# 5_Power_Supplies.net
KiCad netlist of a schematic drawn in Altium Designer
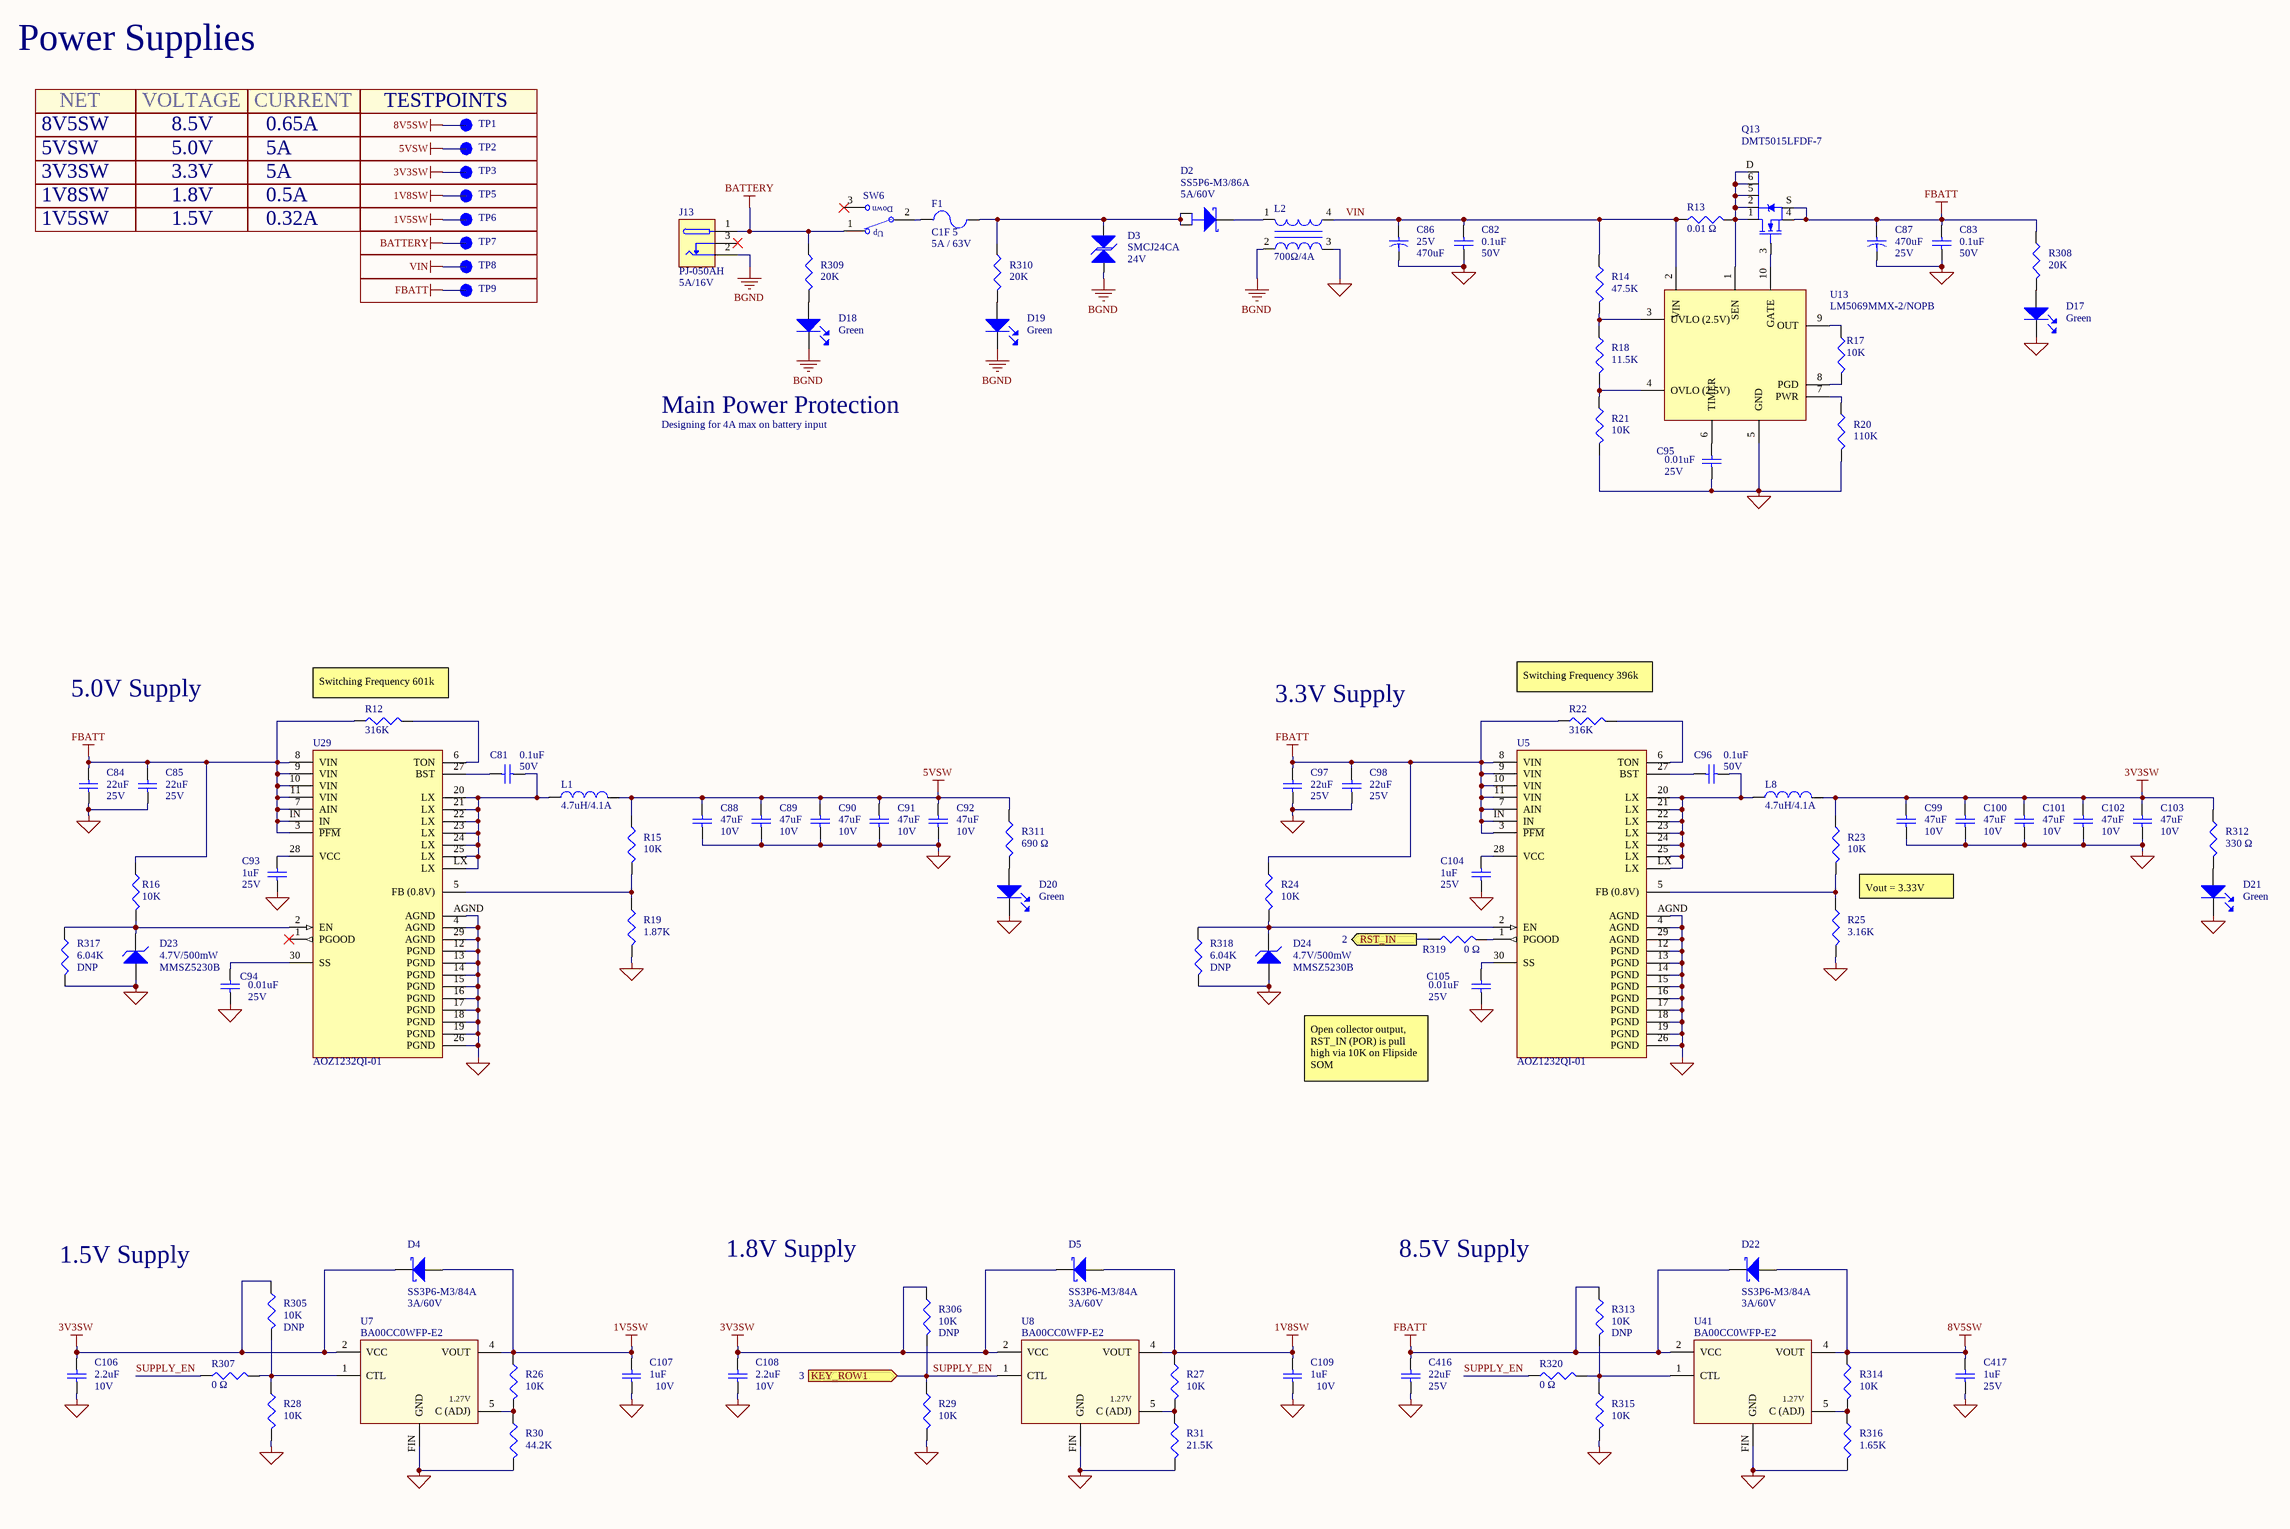
[diagram p0: 5 Power Supplies.SchDoc]

(export (version "E")
  (design (tool "Eeschema 10.0.6"))
  (components
    (comp (ref "C81")
      (value "0.1uF")
      (footprint "CAP_0402")
      (description "Cap, Cer, 0.1uF, 50V, 10%, X5R, 0402")
      (fields
        (field (name "TOLERANCE") "±10%")
        (field (name "MANUFACTURER") "TDK Corporation")
        (field (name "VOLTAGE") "50V")
      )
      (libsource (lib "Firstview") (part "Cap 0.1uF 50V 0402"))
    )
    (comp (ref "C82")
      (value "0.1uF")
      (footprint "CAP_0402")
      (description "Cap, Cer, 0.1uF, 50V, 10%, X5R, 0402")
      (fields
        (field (name "TOLERANCE") "±10%")
        (field (name "MANUFACTURER") "TDK Corporation")
        (field (name "VOLTAGE") "50V")
      )
      (libsource (lib "Firstview") (part "Cap 0.1uF 50V 0402"))
    )
    (comp (ref "C83")
      (value "0.1uF")
      (footprint "CAP_0402")
      (description "Cap, Cer, 0.1uF, 50V, 10%, X5R, 0402")
      (fields
        (field (name "TOLERANCE") "±10%")
        (field (name "MANUFACTURER") "TDK Corporation")
        (field (name "VOLTAGE") "50V")
      )
      (libsource (lib "Firstview") (part "Cap 0.1uF 50V 0402"))
    )
    (comp (ref "C84")
      (value "22uF")
      (footprint "CAP_0805")
      (description "Cap, Cer, 22uF, 25V, 20%, X5R, 0805")
      (fields
        (field (name "TOLERANCE") "±20%")
        (field (name "MANUFACTURER") "Samsung Electro-Mechanics America, Inc")
        (field (name "VOLTAGE") "25V")
      )
      (libsource (lib "Firstview") (part "Cap 22uF 25V 0805"))
    )
    (comp (ref "C85")
      (value "22uF")
      (footprint "CAP_0805")
      (description "Cap, Cer, 22uF, 25V, 20%, X5R, 0805")
      (fields
        (field (name "TOLERANCE") "±20%")
        (field (name "MANUFACTURER") "Samsung Electro-Mechanics America, Inc")
        (field (name "VOLTAGE") "25V")
      )
      (libsource (lib "Firstview") (part "Cap 22uF 25V 0805"))
    )
    (comp (ref "C86")
      (value "470uF")
      (footprint "SMD(8.3x8.3)_EEE-FT1E471AP")
      (description "Cap, Alum, 470uF, 25V, 20%, 80 mOhm, SMD")
      (fields
        (field (name "TOLERANCE") "20%")
        (field (name "MANUFACTURER") "Panasonic Electronic Components")
        (field (name "VOLTAGE") "25V")
      )
      (libsource (lib "Firstview") (part "Cap 470uF 25V"))
    )
    (comp (ref "C87")
      (value "470uF")
      (footprint "SMD(8.3x8.3)_EEE-FT1E471AP")
      (description "Cap, Alum, 470uF, 25V, 20%, 80 mOhm, SMD")
      (fields
        (field (name "TOLERANCE") "20%")
        (field (name "MANUFACTURER") "Panasonic Electronic Components")
        (field (name "VOLTAGE") "25V")
      )
      (libsource (lib "Firstview") (part "Cap 470uF 25V"))
    )
    (comp (ref "C88")
      (value "47uF")
      (footprint "CAP_1206")
      (description "Cap, Cer, 47uF, 10V, 20%, X5R, 1206")
      (fields
        (field (name "TOLERANCE") "±10%")
        (field (name "MANUFACTURER") "Murata Electronics North America")
        (field (name "VOLTAGE") "10V")
      )
      (libsource (lib "Firstview") (part "Cap 47uF 10V 1206"))
    )
    (comp (ref "C89")
      (value "47uF")
      (footprint "CAP_1206")
      (description "Cap, Cer, 47uF, 10V, 20%, X5R, 1206")
      (fields
        (field (name "TOLERANCE") "±10%")
        (field (name "MANUFACTURER") "Murata Electronics North America")
        (field (name "VOLTAGE") "10V")
      )
      (libsource (lib "Firstview") (part "Cap 47uF 10V 1206"))
    )
    (comp (ref "C90")
      (value "47uF")
      (footprint "CAP_1206")
      (description "Cap, Cer, 47uF, 10V, 20%, X5R, 1206")
      (fields
        (field (name "TOLERANCE") "±10%")
        (field (name "MANUFACTURER") "Murata Electronics North America")
        (field (name "VOLTAGE") "10V")
      )
      (libsource (lib "Firstview") (part "Cap 47uF 10V 1206"))
    )
    (comp (ref "C91")
      (value "47uF")
      (footprint "CAP_1206")
      (description "Cap, Cer, 47uF, 10V, 20%, X5R, 1206")
      (fields
        (field (name "TOLERANCE") "±10%")
        (field (name "MANUFACTURER") "Murata Electronics North America")
        (field (name "VOLTAGE") "10V")
      )
      (libsource (lib "Firstview") (part "Cap 47uF 10V 1206"))
    )
    (comp (ref "C92")
      (value "47uF")
      (footprint "CAP_1206")
      (description "Cap, Cer, 47uF, 10V, 20%, X5R, 1206")
      (fields
        (field (name "TOLERANCE") "±10%")
        (field (name "MANUFACTURER") "Murata Electronics North America")
        (field (name "VOLTAGE") "10V")
      )
      (libsource (lib "Firstview") (part "Cap 47uF 10V 1206"))
    )
    (comp (ref "C93")
      (value "1uF")
      (footprint "CAP_0402")
      (description "Cap, Cer, 1uF, 25V, 10%, X5R, 0402")
      (fields
        (field (name "MANUFACTURER") "Taiyo Yuden")
        (field (name "VOLTAGE") "25V")
        (field (name "Comment") "Cap 1uF 25V 0402")
      )
      (libsource (lib "Firstview") (part "Cap 1uF 25V 0402"))
    )
    (comp (ref "C94")
      (value "0.01uF")
      (footprint "CAP_0402")
      (description "Cap, Cer, 0.01uF, 25V, ±10%, X7R, 0402")
      (fields
        (field (name "TOLERANCE") "±10%")
        (field (name "MANUFACTURER") "Murata")
        (field (name "VOLTAGE") "25V")
      )
      (libsource (lib "Firstview") (part "Cap 0.01uF 50V 0402"))
    )
    (comp (ref "C95")
      (value "0.01uF")
      (footprint "CAP_0402")
      (description "Cap, Cer, 0.01uF, 25V, ±10%, X7R, 0402")
      (fields
        (field (name "TOLERANCE") "±10%")
        (field (name "MANUFACTURER") "Murata")
        (field (name "VOLTAGE") "25V")
      )
      (libsource (lib "Firstview") (part "Cap 0.01uF 50V 0402"))
    )
    (comp (ref "C96")
      (value "0.1uF")
      (footprint "CAP_0402")
      (description "Cap, Cer, 0.1uF, 50V, 10%, X5R, 0402")
      (fields
        (field (name "TOLERANCE") "±10%")
        (field (name "MANUFACTURER") "TDK Corporation")
        (field (name "VOLTAGE") "50V")
      )
      (libsource (lib "Firstview") (part "Cap 0.1uF 50V 0402"))
    )
    (comp (ref "C97")
      (value "22uF")
      (footprint "CAP_0805")
      (description "Cap, Cer, 22uF, 25V, 20%, X5R, 0805")
      (fields
        (field (name "TOLERANCE") "±20%")
        (field (name "MANUFACTURER") "Samsung Electro-Mechanics America, Inc")
        (field (name "VOLTAGE") "25V")
      )
      (libsource (lib "Firstview") (part "Cap 22uF 25V 0805"))
    )
    (comp (ref "C98")
      (value "22uF")
      (footprint "CAP_0805")
      (description "Cap, Cer, 22uF, 25V, 20%, X5R, 0805")
      (fields
        (field (name "TOLERANCE") "±20%")
        (field (name "MANUFACTURER") "Samsung Electro-Mechanics America, Inc")
        (field (name "VOLTAGE") "25V")
      )
      (libsource (lib "Firstview") (part "Cap 22uF 25V 0805"))
    )
    (comp (ref "C99")
      (value "47uF")
      (footprint "CAP_1206")
      (description "Cap, Cer, 47uF, 10V, 20%, X5R, 1206")
      (fields
        (field (name "TOLERANCE") "±10%")
        (field (name "MANUFACTURER") "Murata Electronics North America")
        (field (name "VOLTAGE") "10V")
      )
      (libsource (lib "Firstview") (part "Cap 47uF 10V 1206"))
    )
    (comp (ref "C100")
      (value "47uF")
      (footprint "CAP_1206")
      (description "Cap, Cer, 47uF, 10V, 20%, X5R, 1206")
      (fields
        (field (name "TOLERANCE") "±10%")
        (field (name "MANUFACTURER") "Murata Electronics North America")
        (field (name "VOLTAGE") "10V")
      )
      (libsource (lib "Firstview") (part "Cap 47uF 10V 1206"))
    )
    (comp (ref "C101")
      (value "47uF")
      (footprint "CAP_1206")
      (description "Cap, Cer, 47uF, 10V, 20%, X5R, 1206")
      (fields
        (field (name "TOLERANCE") "±10%")
        (field (name "MANUFACTURER") "Murata Electronics North America")
        (field (name "VOLTAGE") "10V")
      )
      (libsource (lib "Firstview") (part "Cap 47uF 10V 1206"))
    )
    (comp (ref "C102")
      (value "47uF")
      (footprint "CAP_1206")
      (description "Cap, Cer, 47uF, 10V, 20%, X5R, 1206")
      (fields
        (field (name "TOLERANCE") "±10%")
        (field (name "MANUFACTURER") "Murata Electronics North America")
        (field (name "VOLTAGE") "10V")
      )
      (libsource (lib "Firstview") (part "Cap 47uF 10V 1206"))
    )
    (comp (ref "C103")
      (value "47uF")
      (footprint "CAP_1206")
      (description "Cap, Cer, 47uF, 10V, 20%, X5R, 1206")
      (fields
        (field (name "TOLERANCE") "±10%")
        (field (name "MANUFACTURER") "Murata Electronics North America")
        (field (name "VOLTAGE") "10V")
      )
      (libsource (lib "Firstview") (part "Cap 47uF 10V 1206"))
    )
    (comp (ref "C104")
      (value "1uF")
      (footprint "CAP_0402")
      (description "Cap, Cer, 1uF, 25V, 10%, X5R, 0402")
      (fields
        (field (name "MANUFACTURER") "Taiyo Yuden")
        (field (name "VOLTAGE") "25V")
        (field (name "Comment") "Cap 1uF 25V 0402")
      )
      (libsource (lib "Firstview") (part "Cap 1uF 25V 0402"))
    )
    (comp (ref "C105")
      (value "0.01uF")
      (footprint "CAP_0402")
      (description "Cap, Cer, 0.01uF, 25V, ±10%, X7R, 0402")
      (fields
        (field (name "TOLERANCE") "±10%")
        (field (name "MANUFACTURER") "Murata")
        (field (name "VOLTAGE") "25V")
      )
      (libsource (lib "Firstview") (part "Cap 0.01uF 50V 0402"))
    )
    (comp (ref "C106")
      (value "2.2uF")
      (footprint "CAP_0402")
      (description "Cap, Cer, 2.2uF, 10V, 10%, X5R, 0402")
      (fields
        (field (name "MANUFACTURER") "Kemet")
        (field (name "VOLTAGE") "10V")
        (field (name "Comment") "Cap 2.2uF 10V 0402")
      )
      (libsource (lib "Firstview") (part "Cap 2.2uF 10V 0402"))
    )
    (comp (ref "C107")
      (value "1uF")
      (footprint "CAP_0402")
      (description "Cap, Cer, 1uF, 10V, ±10%, X5R, 0402")
      (fields
        (field (name "MANUFACTURER") "Yageo")
        (field (name "VOLTAGE") "10V")
        (field (name "Comment") "Cap 1uF 10V 0402")
      )
      (libsource (lib "Firstview") (part "Cap 1uF 10V 0402"))
    )
    (comp (ref "C108")
      (value "2.2uF")
      (footprint "CAP_0402")
      (description "Cap, Cer, 2.2uF, 10V, 10%, X5R, 0402")
      (fields
        (field (name "MANUFACTURER") "Kemet")
        (field (name "VOLTAGE") "10V")
        (field (name "Comment") "Cap 2.2uF 10V 0402")
      )
      (libsource (lib "Firstview") (part "Cap 2.2uF 10V 0402"))
    )
    (comp (ref "C109")
      (value "1uF")
      (footprint "CAP_0402")
      (description "Cap, Cer, 1uF, 10V, ±10%, X5R, 0402")
      (fields
        (field (name "MANUFACTURER") "Yageo")
        (field (name "VOLTAGE") "10V")
        (field (name "Comment") "Cap 1uF 10V 0402")
      )
      (libsource (lib "Firstview") (part "Cap 1uF 10V 0402"))
    )
    (comp (ref "C416")
      (value "22uF")
      (footprint "CAP_0805")
      (description "Cap, Cer, 22uF, 25V, 20%, X5R, 0805")
      (fields
        (field (name "TOLERANCE") "±20%")
        (field (name "MANUFACTURER") "Samsung Electro-Mechanics America, Inc")
        (field (name "VOLTAGE") "25V")
      )
      (libsource (lib "Firstview") (part "Cap 22uF 25V 0805"))
    )
    (comp (ref "C417")
      (value "1uF")
      (footprint "CAP_0402")
      (description "Cap, Cer, 1uF, 25V, 10%, X5R, 0402")
      (fields
        (field (name "MANUFACTURER") "Taiyo Yuden")
        (field (name "VOLTAGE") "25V")
        (field (name "Comment") "Cap 1uF 25V 0402")
      )
      (libsource (lib "Firstview") (part "Cap 1uF 25V 0402"))
    )
    (comp (ref "D2")
      (value "SS5P6-M3/86A")
      (footprint "TO-277A_SS5P6")
      (description "Diode, Schottky, 5A, 60V, TO-277A")
      (fields
        (field (name "MANUFACTURER") "Vishay Semiconductor Diodes Division")
        (field (name "ALTIUM_VALUE") "5A/60V")
      )
      (libsource (lib "Firstview") (part "SS5P6-M3/86A"))
    )
    (comp (ref "D3")
      (value "SMCJ24CA")
      (footprint "SMC_SMCJ24CA")
      (description "Diode, TVS, 24V, 1500W, SMC")
      (fields (field (name "MANUFACTURER") "Littelfuse Inc") (field (name "ALTIUM_VALUE") "24V"))
      (libsource (lib "Firstview") (part "SMCJ24CA"))
    )
    (comp (ref "D4")
      (value "SS3P6-M3/84A")
      (footprint "DO-220AA_SS3P6-M3/84A")
      (description "Diode, Schottky, 3A, 60V, DO-220AA")
      (fields (field (name "MANUFACTURER") "Vishay") (field (name "ALTIUM_VALUE") "3A/60V"))
      (libsource (lib "Firstview") (part "SS3P6-M3/84A"))
    )
    (comp (ref "D5")
      (value "SS3P6-M3/84A")
      (footprint "DO-220AA_SS3P6-M3/84A")
      (description "Diode, Schottky, 3A, 60V, DO-220AA")
      (fields (field (name "MANUFACTURER") "Vishay") (field (name "ALTIUM_VALUE") "3A/60V"))
      (libsource (lib "Firstview") (part "SS3P6-M3/84A"))
    )
    (comp (ref "D17")
      (value "Green")
      (footprint "LED_0603")
      (description "Led, Green, 2mA, 1.7V, 0603")
      (fields
        (field (name "MANUFACTURER") "OSRAM Opto Semiconductors Inc")
        (field (name "Comment") "LG L29K-G2J1-24-Z")
      )
      (libsource (lib "Firstview") (part "LG L29K-G2J1-24-Z"))
    )
    (comp (ref "D18")
      (value "Green")
      (footprint "LED_0603")
      (description "Led, Green, 2mA, 1.7V, 0603")
      (fields
        (field (name "MANUFACTURER") "OSRAM Opto Semiconductors Inc")
        (field (name "Comment") "LG L29K-G2J1-24-Z")
      )
      (libsource (lib "Firstview") (part "LG L29K-G2J1-24-Z"))
    )
    (comp (ref "D19")
      (value "Green")
      (footprint "LED_0603")
      (description "Led, Green, 2mA, 1.7V, 0603")
      (fields
        (field (name "MANUFACTURER") "OSRAM Opto Semiconductors Inc")
        (field (name "Comment") "LG L29K-G2J1-24-Z")
      )
      (libsource (lib "Firstview") (part "LG L29K-G2J1-24-Z"))
    )
    (comp (ref "D20")
      (value "Green")
      (footprint "LED_0603")
      (description "Led, Green, 2mA, 1.7V, 0603")
      (fields
        (field (name "MANUFACTURER") "OSRAM Opto Semiconductors Inc")
        (field (name "Comment") "LG L29K-G2J1-24-Z")
      )
      (libsource (lib "Firstview") (part "LG L29K-G2J1-24-Z"))
    )
    (comp (ref "D21")
      (value "Green")
      (footprint "LED_0603")
      (description "Led, Green, 2mA, 1.7V, 0603")
      (fields
        (field (name "MANUFACTURER") "OSRAM Opto Semiconductors Inc")
        (field (name "Comment") "LG L29K-G2J1-24-Z")
      )
      (libsource (lib "Firstview") (part "LG L29K-G2J1-24-Z"))
    )
    (comp (ref "D22")
      (value "SS3P6-M3/84A")
      (footprint "DO-220AA_SS3P6-M3/84A")
      (description "Diode, Schottky, 3A, 60V, DO-220AA")
      (fields (field (name "MANUFACTURER") "Vishay") (field (name "ALTIUM_VALUE") "3A/60V"))
      (libsource (lib "Firstview") (part "SS3P6-M3/84A"))
    )
    (comp (ref "D23")
      (value "MMSZ5230B")
      (footprint "SOD-123_MMSZ5230B")
      (description "Diode, Zener, 4.7V, 500mW, SOD-123")
      (fields (field (name "MANUFACTURER") "Diodes Incorporated") (field (name "ALTIUM_VALUE") "4.7V/500mW"))
      (libsource (lib "Firstview") (part "MMSZ5230B"))
    )
    (comp (ref "D24")
      (value "MMSZ5230B")
      (footprint "SOD-123_MMSZ5230B")
      (description "Diode, Zener, 4.7V, 500mW, SOD-123")
      (fields (field (name "MANUFACTURER") "Diodes Incorporated") (field (name "ALTIUM_VALUE") "4.7V/500mW"))
      (libsource (lib "Firstview") (part "MMSZ5230B"))
    )
    (comp (ref "F1")
      (value "C1F 5")
      (footprint "FUSE_1206")
      (description "Fuse, 5A, 63V, 1206")
      (fields (field (name "MANUFACTURER") "Bel Fuse Inc") (field (name "ALTIUM_VALUE") "5A / 63V"))
      (libsource (lib "Firstview") (part "C1F 5"))
    )
    (comp (ref "J13")
      (value "PJ-050AH")
      (footprint "CONN_PJ-050AH")
      (description "Conn, Power Jack, 2.1x5mm, R/A, TH")
      (fields
        (field (name "VOLTAGE") "16V")
        (field (name "MANUFACTURER") "CUI Inc")
        (field (name "ALTIUM_VALUE") "5A/16V")
      )
      (libsource (lib "Firstview") (part "PJ-050AH"))
    )
    (comp (ref "L1")
      (value "4.7uH/4.1A")
      (footprint "IND_NRS8040T4R7NJGJ")
      (description "Ind, Power, 4.7uH, 4.1A, 23.4mOhm, Shielded, SMD")
      (fields (field (name "MANUFACTURER") "Taiyo Yuden") (field (name "Comment") "NRS8040T4R7NJGJ"))
      (libsource (lib "Firstview") (part "NRS8040T4R7NJGJ"))
    )
    (comp (ref "L2")
      (value "700Ω/4A")
      (footprint "IND_ACM70V-701-2PL-TL00")
      (description "Ind, Choke, Common Mode, 700R, 4A, SMD")
      (fields (field (name "MANUFACTURER") "TDK Corporation") (field (name "Comment") "ACM70V-701-2PL-TL00"))
      (libsource (lib "Firstview") (part "ACM70V-701-2PL-TL00"))
    )
    (comp (ref "L8")
      (value "4.7uH/4.1A")
      (footprint "IND_NRS8040T4R7NJGJ")
      (description "Ind, Power, 4.7uH, 4.1A, 23.4mOhm, Shielded, SMD")
      (fields (field (name "MANUFACTURER") "Taiyo Yuden") (field (name "Comment") "NRS8040T4R7NJGJ"))
      (libsource (lib "Firstview") (part "NRS8040T4R7NJGJ"))
    )
    (comp (ref "Q13")
      (value "DMT5015LFDF-7")
      (footprint "UDFN-6_DMT5015LFDF-7")
      (description "Transistor, N-MOS, 9.1A, 50V, 15 mOhm, UDFN-6")
      (fields (field (name "MANUFACTURER") "Diodes Incorporated") (field (name "VOLTAGE") "50V"))
      (libsource (lib "Firstview") (part "DMT5015LFDF-7"))
    )
    (comp (ref "R12")
      (value "316K")
      (footprint "RES_0402")
      (description "Res, 316K, 0.063W, 1%, 0402")
      (fields
        (field (name "MANUFACTURER") "Stackpole Electronics Inc")
        (field (name "Comment") "Res 316K 0.063W")
      )
      (libsource (lib "Firstview") (part "Res 316K 0.063W"))
    )
    (comp (ref "R13")
      (value "0.01 Ω")
      (footprint "RES_1210")
      (description "Res, 0.01 ohm, 0.5W, 1%, 1210")
      (fields (field (name "MANUFACTURER") "Yageo") (field (name "Comment") "Res 0.01 ohm 0.5W"))
      (libsource (lib "Firstview") (part "Res 0.01 ohm 0.5W"))
    )
    (comp (ref "R14")
      (value "47.5K")
      (footprint "RES_0402")
      (description "Res, 47.5K, 0.063W, 1%, 0402")
      (fields
        (field (name "MANUFACTURER") "Stackpole Electronics Inc")
        (field (name "Comment") "Res 47.5K 0.063W")
      )
      (libsource (lib "Firstview") (part "Res 47.5K 0.063W"))
    )
    (comp (ref "R15")
      (value "10K")
      (footprint "RES_0402")
      (description "Res, 10K, 1/16W, 1%, 0402")
      (fields (field (name "MANUFACTURER") "Yageo") (field (name "Comment") "Res 10K 0.063W"))
      (libsource (lib "Firstview") (part "Res 10K 0.063W"))
    )
    (comp (ref "R16")
      (value "10K")
      (footprint "RES_0402")
      (description "Res, 10K, 1/16W, 1%, 0402")
      (fields (field (name "MANUFACTURER") "Yageo") (field (name "Comment") "Res 10K 0.063W"))
      (libsource (lib "Firstview") (part "Res 10K 0.063W"))
    )
    (comp (ref "R17")
      (value "10K")
      (footprint "RES_0402")
      (description "Res, 10K, 1/16W, 1%, 0402")
      (fields (field (name "MANUFACTURER") "Yageo") (field (name "Comment") "Res 10K 0.063W"))
      (libsource (lib "Firstview") (part "Res 10K 0.063W"))
    )
    (comp (ref "R18")
      (value "11.5K")
      (footprint "RES_0402")
      (description "Res, 11.5K, 0.063W, 1%, 0402")
      (fields
        (field (name "MANUFACTURER") "Stackpole Electronics Inc")
        (field (name "Comment") "Res 11.5K 0.063W")
      )
      (libsource (lib "Firstview") (part "Res 11.5K 0.063W"))
    )
    (comp (ref "R19")
      (value "1.87K")
      (footprint "RES_0402")
      (description "Res, 1.87K, 0.063W, 1%, 0402")
      (fields (field (name "TOLERANCE") "1%") (field (name "MANUFACTURER") "Stackpole Electronics Inc"))
      (libsource (lib "Firstview") (part "Res 1.87K 0.063W"))
    )
    (comp (ref "R20")
      (value "110K")
      (footprint "RES_0402")
      (description "Res, 110K, 0.063W, 5%, 0402")
      (fields (field (name "TOLERANCE") "5%") (field (name "MANUFACTURER") "Rohm Semiconductor"))
      (libsource (lib "Firstview") (part "Res 110K 0.063W"))
    )
    (comp (ref "R21")
      (value "10K")
      (footprint "RES_0402")
      (description "Res, 10K, 1/16W, 1%, 0402")
      (fields (field (name "MANUFACTURER") "Yageo") (field (name "Comment") "Res 10K 0.063W"))
      (libsource (lib "Firstview") (part "Res 10K 0.063W"))
    )
    (comp (ref "R22")
      (value "316K")
      (footprint "RES_0402")
      (description "Res, 316K, 0.063W, 1%, 0402")
      (fields
        (field (name "MANUFACTURER") "Stackpole Electronics Inc")
        (field (name "Comment") "Res 316K 0.063W")
      )
      (libsource (lib "Firstview") (part "Res 316K 0.063W"))
    )
    (comp (ref "R23")
      (value "10K")
      (footprint "RES_0402")
      (description "Res, 10K, 1/16W, 1%, 0402")
      (fields (field (name "MANUFACTURER") "Yageo") (field (name "Comment") "Res 10K 0.063W"))
      (libsource (lib "Firstview") (part "Res 10K 0.063W"))
    )
    (comp (ref "R24")
      (value "10K")
      (footprint "RES_0402")
      (description "Res, 10K, 1/16W, 1%, 0402")
      (fields (field (name "MANUFACTURER") "Yageo") (field (name "Comment") "Res 10K 0.063W"))
      (libsource (lib "Firstview") (part "Res 10K 0.063W"))
    )
    (comp (ref "R25")
      (value "3.16K")
      (footprint "RES_0402")
      (description "Res, 3.16K, 0.063W, 1%, 0402")
      (fields
        (field (name "MANUFACTURER") "Stackpole Electronics Inc")
        (field (name "Comment") "Res 3.16K 0.063W")
      )
      (libsource (lib "Firstview") (part "Res 3.16K 0.063W"))
    )
    (comp (ref "R26")
      (value "10K")
      (footprint "RES_0402")
      (description "Res, 10K, 1/16W, 1%, 0402")
      (fields (field (name "MANUFACTURER") "Yageo") (field (name "Comment") "Res 10K 0.063W"))
      (libsource (lib "Firstview") (part "Res 10K 0.063W"))
    )
    (comp (ref "R27")
      (value "10K")
      (footprint "RES_0402")
      (description "Res, 10K, 1/16W, 1%, 0402")
      (fields (field (name "MANUFACTURER") "Yageo") (field (name "Comment") "Res 10K 0.063W"))
      (libsource (lib "Firstview") (part "Res 10K 0.063W"))
    )
    (comp (ref "R28")
      (value "10K")
      (footprint "RES_0402")
      (description "Res, 10K, 1/16W, 1%, 0402")
      (fields (field (name "MANUFACTURER") "Yageo") (field (name "Comment") "Res 10K 0.063W"))
      (libsource (lib "Firstview") (part "Res 10K 0.063W"))
    )
    (comp (ref "R29")
      (value "10K")
      (footprint "RES_0402")
      (description "Res, 10K, 1/16W, 1%, 0402")
      (fields (field (name "MANUFACTURER") "Yageo") (field (name "Comment") "Res 10K 0.063W"))
      (libsource (lib "Firstview") (part "Res 10K 0.063W"))
    )
    (comp (ref "R30")
      (value "44.2K")
      (footprint "RES_0402")
      (description "Res, 44.2K, 0.063W, 1%, 0402")
      (fields
        (field (name "MANUFACTURER") "Stackpole Electronics Inc")
        (field (name "Comment") "Res 44.2K 0.063W")
      )
      (libsource (lib "Firstview") (part "Res 44.2K 0.063W"))
    )
    (comp (ref "R31")
      (value "21.5K")
      (footprint "RES_0402")
      (description "Res, 21.5K, 0.063W, 1%, 0402")
      (fields
        (field (name "MANUFACTURER") "Panasonic Electronic Components")
        (field (name "Comment") "Res 21.5K 0.063W")
      )
      (libsource (lib "Firstview") (part "Res 21.5K 0.063W"))
    )
    (comp (ref "R305")
      (value "10K")
      (footprint "RES_0402")
      (description "Res, 10K, 1/16W, 1%, 0402")
      (fields
        (field (name "DNP") "DNP")
        (field (name "MANUFACTURER") "Yageo")
        (field (name "Comment") "Res 10K 0.063W")
      )
      (libsource (lib "Firstview") (part "Res 10K 0.063W"))
    )
    (comp (ref "R306")
      (value "10K")
      (footprint "RES_0402")
      (description "Res, 10K, 1/16W, 1%, 0402")
      (fields
        (field (name "DNP") "DNP")
        (field (name "MANUFACTURER") "Yageo")
        (field (name "Comment") "Res 10K 0.063W")
      )
      (libsource (lib "Firstview") (part "Res 10K 0.063W"))
    )
    (comp (ref "R307")
      (value "0 Ω")
      (footprint "RES_0402")
      (description "Res, 0 ohm, 1/16W, 0402")
      (fields (field (name "MANUFACTURER") "Vishay Dale") (field (name "Comment") "Res 0 ohm 0.1W"))
      (libsource (lib "Firstview") (part "Res 0 ohm 0.1W"))
    )
    (comp (ref "R308")
      (value "20K")
      (footprint "RES_0402")
      (description "Res, 20K, 0.1W, 1%, 0402")
      (fields
        (field (name "MANUFACTURER") "Panasonic Electronic Components")
        (field (name "Comment") "Res 20K 0.1W")
      )
      (libsource (lib "Firstview") (part "Res 20K 0.1W"))
    )
    (comp (ref "R309")
      (value "20K")
      (footprint "RES_0402")
      (description "Res, 20K, 0.1W, 1%, 0402")
      (fields
        (field (name "MANUFACTURER") "Panasonic Electronic Components")
        (field (name "Comment") "Res 20K 0.1W")
      )
      (libsource (lib "Firstview") (part "Res 20K 0.1W"))
    )
    (comp (ref "R310")
      (value "20K")
      (footprint "RES_0402")
      (description "Res, 20K, 0.1W, 1%, 0402")
      (fields
        (field (name "MANUFACTURER") "Panasonic Electronic Components")
        (field (name "Comment") "Res 20K 0.1W")
      )
      (libsource (lib "Firstview") (part "Res 20K 0.1W"))
    )
    (comp (ref "R311")
      (value "690 Ω")
      (footprint "RES_0402")
      (description "Res, 680R, 0.063W, 1%, 0402")
      (fields (field (name "TOLERANCE") "±1%") (field (name "MANUFACTURER") "Stackpole Electronics Inc"))
      (libsource (lib "Firstview") (part "Res 680R 0.063W"))
    )
    (comp (ref "R312")
      (value "330 Ω")
      (footprint "RES_0402")
      (description "Res, 330R, 0.063W, 1%, 0402")
      (fields (field (name "MANUFACTURER") "Yageo") (field (name "Comment") "Res 330R 0.063W"))
      (libsource (lib "Firstview") (part "Res 330R 0.063W"))
    )
    (comp (ref "R313")
      (value "10K")
      (footprint "RES_0402")
      (description "Res, 10K, 1/16W, 1%, 0402")
      (fields (field (name "MANUFACTURER") "Yageo") (field (name "Comment") "Res 10K 0.063W"))
      (libsource (lib "Firstview") (part "Res 10K 0.063W"))
    )
    (comp (ref "R314")
      (value "10K")
      (footprint "RES_0402")
      (description "Res, 10K, 1/16W, 1%, 0402")
      (fields (field (name "MANUFACTURER") "Yageo") (field (name "Comment") "Res 10K 0.063W"))
      (libsource (lib "Firstview") (part "Res 10K 0.063W"))
    )
    (comp (ref "R315")
      (value "10K")
      (footprint "RES_0402")
      (description "Res, 10K, 1/16W, 1%, 0402")
      (fields
        (field (name "DNP") "DNP")
        (field (name "MANUFACTURER") "Yageo")
        (field (name "Comment") "Res 10K 0.063W")
      )
      (libsource (lib "Firstview") (part "Res 10K 0.063W"))
    )
    (comp (ref "R316")
      (value "1.65K")
      (footprint "RES_0402")
      (description "Res, 1.65K, 0.1W, 1%, 0402")
      (fields (field (name "TOLERANCE") "1%") (field (name "MANUFACTURER") "Panasonic Electronic Components"))
      (libsource (lib "Firstview") (part "Res 1.65K 0.1W"))
    )
    (comp (ref "R317")
      (value "6.04K")
      (footprint "RES_0402")
      (description "Res, 6.04K, 0.063W, 1%, 0402")
      (fields
        (field (name "TOLERANCE") "±1%")
        (field (name "DNP") "DNP")
        (field (name "MANUFACTURER") "Yageo")
      )
      (libsource (lib "Firstview") (part "Res 6.04K 0.063W"))
    )
    (comp (ref "R318")
      (value "6.04K")
      (footprint "RES_0402")
      (description "Res, 6.04K, 0.063W, 1%, 0402")
      (fields
        (field (name "TOLERANCE") "±1%")
        (field (name "DNP") "DNP")
        (field (name "MANUFACTURER") "Yageo")
      )
      (libsource (lib "Firstview") (part "Res 6.04K 0.063W"))
    )
    (comp (ref "R319")
      (value "0 Ω")
      (footprint "RES_0402")
      (description "Res, 0 ohm, 1/16W, 0402")
      (fields (field (name "MANUFACTURER") "Vishay Dale") (field (name "Comment") "Res 0 ohm 0.1W"))
      (libsource (lib "Firstview") (part "Res 0 ohm 0.1W"))
    )
    (comp (ref "R320")
      (value "0 Ω")
      (footprint "RES_0402")
      (description "Res, 0 ohm, 1/16W, 0402")
      (fields (field (name "MANUFACTURER") "Vishay Dale") (field (name "Comment") "Res 0 ohm 0.1W"))
      (libsource (lib "Firstview") (part "Res 0 ohm 0.1W"))
    )
    (comp (ref "SW6")
      (value "M2012S3S2W40")
      (footprint "SW_M2012S3S2W40")
      (description "Switch, Toggle, SPDT, 30V, 4A, RT, TH")
      (fields (field (name "MANUFACTURER") "NKK Switches"))
      (libsource (lib "Firstview") (part "M2012S3S2W40"))
    )
    (comp (ref "TP1")
      (value "TP")
      (footprint "TP_TH_12_20")
      (description "Testpad")
      (libsource (lib "Firstview") (part "TestPoint"))
    )
    (comp (ref "TP2")
      (value "TP")
      (footprint "TP_TH_12_20")
      (description "Testpad")
      (libsource (lib "Firstview") (part "TestPoint"))
    )
    (comp (ref "TP3")
      (value "TP")
      (footprint "TP_TH_12_20")
      (description "Testpad")
      (libsource (lib "Firstview") (part "TestPoint"))
    )
    (comp (ref "TP5")
      (value "TP")
      (footprint "TP_TH_12_20")
      (description "Testpad")
      (libsource (lib "Firstview") (part "TestPoint"))
    )
    (comp (ref "TP6")
      (value "TP")
      (footprint "TP_TH_12_20")
      (description "Testpad")
      (libsource (lib "Firstview") (part "TestPoint"))
    )
    (comp (ref "TP7")
      (value "TP")
      (footprint "TP_TH_12_20")
      (description "Testpad")
      (libsource (lib "Firstview") (part "TestPoint"))
    )
    (comp (ref "TP8")
      (value "TP")
      (footprint "TP_TH_12_20")
      (description "Testpad")
      (libsource (lib "Firstview") (part "TestPoint"))
    )
    (comp (ref "TP9")
      (value "TP")
      (footprint "TP_TH_12_20")
      (description "Testpad")
      (libsource (lib "Firstview") (part "TestPoint"))
    )
    (comp (ref "U5")
      (value "AOZ1232QI-01")
      (footprint "QFN(5x5)_AOZ1232QI-01")
      (description "IC, Power, Buck, 6A, AOZ1232QI-01, 30-QFN (5x5)")
      (fields (field (name "MANUFACTURER") "Alpha & Omega"))
      (libsource (lib "Firstview") (part "AOZ1232QI-01"))
    )
    (comp (ref "U7")
      (value "BA00CC0WFP-E2")
      (footprint "TO-252-5_BA00CC0WFP-E2")
      (description "LDO, Adj., 1A, 4-25V, TO-252-2")
      (fields (field (name "MANUFACTURER") "Rohm Semiconductor"))
      (libsource (lib "Firstview") (part "BA00CC0WFP-E2"))
    )
    (comp (ref "U8")
      (value "BA00CC0WFP-E2")
      (footprint "TO-252-5_BA00CC0WFP-E2")
      (description "LDO, Adj., 1A, 4-25V, TO-252-2")
      (fields (field (name "MANUFACTURER") "Rohm Semiconductor"))
      (libsource (lib "Firstview") (part "BA00CC0WFP-E2"))
    )
    (comp (ref "U13")
      (value "LM5069MMX-2/NOPB")
      (footprint "VSSOP-10_LM5069")
      (description "IC, Power, Hot Swap Controller, VSSOP-10")
      (fields (field (name "MANUFACTURER") "Texas Instruments"))
      (libsource (lib "Firstview") (part "LM5069MMX-2/NOPB"))
    )
    (comp (ref "U29")
      (value "AOZ1232QI-01")
      (footprint "QFN(5x5)_AOZ1232QI-01")
      (description "IC, Power, Buck, 6A, AOZ1232QI-01, 30-QFN (5x5)")
      (fields (field (name "MANUFACTURER") "Alpha & Omega"))
      (libsource (lib "Firstview") (part "AOZ1232QI-01"))
    )
    (comp (ref "U41")
      (value "BA00CC0WFP-E2")
      (footprint "TO-252-5_BA00CC0WFP-E2")
      (description "LDO, Adj., 1A, 4-25V, TO-252-2")
      (fields (field (name "MANUFACTURER") "Rohm Semiconductor"))
      (libsource (lib "Firstview") (part "BA00CC0WFP-E2"))
    )
  )
  (nets
    (net (code "1") (name "/RST_IN") (class "Default")
      (node (ref "R319") (pin "1") (pinfunction "1_1") (pintype "passive"))
    )
    (net (code "2") (name "/SUPPLY_EN") (class "Default")
      (node (ref "R29") (pin "1") (pinfunction "1_1") (pintype "passive"))
      (node (ref "R306") (pin "2") (pinfunction "2_2") (pintype "passive"))
      (node (ref "R307") (pin "1") (pinfunction "1_1") (pintype "passive"))
      (node (ref "R320") (pin "1") (pinfunction "1_1") (pintype "passive"))
      (node (ref "U8") (pin "1") (pinfunction "CTL_1") (pintype "passive"))
    )
    (net (code "3") (name "1V5SW") (class "Default")
      (node (ref "C107") (pin "1") (pinfunction "1_1") (pintype "passive"))
      (node (ref "D4") (pin "A") (pinfunction "A_A") (pintype "passive"))
      (node (ref "R26") (pin "1") (pinfunction "1_1") (pintype "passive"))
      (node (ref "TP6") (pin "1") (pinfunction "1_1") (pintype "passive"))
      (node (ref "U7") (pin "4") (pinfunction "VOUT_4") (pintype "power_in"))
    )
    (net (code "4") (name "1V8SW") (class "Default")
      (node (ref "C109") (pin "1") (pinfunction "1_1") (pintype "passive"))
      (node (ref "D5") (pin "A") (pinfunction "A_A") (pintype "passive"))
      (node (ref "R27") (pin "1") (pinfunction "1_1") (pintype "passive"))
      (node (ref "TP5") (pin "1") (pinfunction "1_1") (pintype "passive"))
      (node (ref "U8") (pin "4") (pinfunction "VOUT_4") (pintype "power_in"))
    )
    (net (code "5") (name "3V3SW") (class "Default")
      (node (ref "C100") (pin "1") (pinfunction "1_1") (pintype "passive"))
      (node (ref "C101") (pin "1") (pinfunction "1_1") (pintype "passive"))
      (node (ref "C102") (pin "1") (pinfunction "1_1") (pintype "passive"))
      (node (ref "C103") (pin "1") (pinfunction "1_1") (pintype "passive"))
      (node (ref "C106") (pin "1") (pinfunction "1_1") (pintype "passive"))
      (node (ref "C108") (pin "1") (pinfunction "1_1") (pintype "passive"))
      (node (ref "C99") (pin "1") (pinfunction "1_1") (pintype "passive"))
      (node (ref "D4") (pin "K") (pinfunction "K_K") (pintype "passive"))
      (node (ref "D5") (pin "K") (pinfunction "K_K") (pintype "passive"))
      (node (ref "L8") (pin "2") (pinfunction "2_2") (pintype "passive"))
      (node (ref "R23") (pin "1") (pinfunction "1_1") (pintype "passive"))
      (node (ref "R305") (pin "1") (pinfunction "1_1") (pintype "passive"))
      (node (ref "R306") (pin "1") (pinfunction "1_1") (pintype "passive"))
      (node (ref "R312") (pin "1") (pinfunction "1_1") (pintype "passive"))
      (node (ref "TP3") (pin "1") (pinfunction "1_1") (pintype "passive"))
      (node (ref "U7") (pin "2") (pinfunction "VCC_2") (pintype "power_in"))
      (node (ref "U8") (pin "2") (pinfunction "VCC_2") (pintype "power_in"))
    )
    (net (code "6") (name "5VSW") (class "Default")
      (node (ref "C88") (pin "1") (pinfunction "1_1") (pintype "passive"))
      (node (ref "C89") (pin "1") (pinfunction "1_1") (pintype "passive"))
      (node (ref "C90") (pin "1") (pinfunction "1_1") (pintype "passive"))
      (node (ref "C91") (pin "1") (pinfunction "1_1") (pintype "passive"))
      (node (ref "C92") (pin "1") (pinfunction "1_1") (pintype "passive"))
      (node (ref "L1") (pin "2") (pinfunction "2_2") (pintype "passive"))
      (node (ref "R15") (pin "1") (pinfunction "1_1") (pintype "passive"))
      (node (ref "R311") (pin "1") (pinfunction "1_1") (pintype "passive"))
      (node (ref "TP2") (pin "1") (pinfunction "1_1") (pintype "passive"))
    )
    (net (code "7") (name "8V5SW") (class "Default")
      (node (ref "C417") (pin "1") (pinfunction "1_1") (pintype "passive"))
      (node (ref "D22") (pin "A") (pinfunction "A_A") (pintype "passive"))
      (node (ref "R314") (pin "1") (pinfunction "1_1") (pintype "passive"))
      (node (ref "TP1") (pin "1") (pinfunction "1_1") (pintype "passive"))
      (node (ref "U41") (pin "4") (pinfunction "VOUT_4") (pintype "power_in"))
    )
    (net (code "8") (name "BATTERY") (class "Default")
      (node (ref "J13") (pin "1") (pinfunction "1_1") (pintype "passive"))
      (node (ref "R309") (pin "1") (pinfunction "1_1") (pintype "passive"))
      (node (ref "SW6") (pin "1") (pinfunction "1_1") (pintype "passive"))
      (node (ref "TP7") (pin "1") (pinfunction "1_1") (pintype "passive"))
    )
    (net (code "9") (name "BGND") (class "Default")
      (node (ref "D18") (pin "K") (pinfunction "K_K") (pintype "passive"))
      (node (ref "D19") (pin "K") (pinfunction "K_K") (pintype "passive"))
      (node (ref "D3") (pin "2") (pinfunction "2_2") (pintype "passive"))
      (node (ref "J13") (pin "2") (pinfunction "2_2") (pintype "passive"))
      (node (ref "L2") (pin "2") (pinfunction "2_2") (pintype "passive"))
    )
    (net (code "10") (name "FBATT") (class "Default")
      (node (ref "C416") (pin "1") (pinfunction "1_1") (pintype "passive"))
      (node (ref "C83") (pin "1") (pinfunction "1_1") (pintype "passive"))
      (node (ref "C84") (pin "1") (pinfunction "1_1") (pintype "passive"))
      (node (ref "C85") (pin "1") (pinfunction "1_1") (pintype "passive"))
      (node (ref "C87") (pin "1") (pinfunction "1_1") (pintype "passive"))
      (node (ref "C97") (pin "1") (pinfunction "1_1") (pintype "passive"))
      (node (ref "C98") (pin "1") (pinfunction "1_1") (pintype "passive"))
      (node (ref "D22") (pin "K") (pinfunction "K_K") (pintype "passive"))
      (node (ref "Q13") (pin "4") (pinfunction "S_4") (pintype "passive"))
      (node (ref "Q13") (pin "S") (pinfunction "S_S") (pintype "passive"))
      (node (ref "R12") (pin "1") (pinfunction "1_1") (pintype "passive"))
      (node (ref "R16") (pin "1") (pinfunction "1_1") (pintype "passive"))
      (node (ref "R22") (pin "1") (pinfunction "1_1") (pintype "passive"))
      (node (ref "R24") (pin "1") (pinfunction "1_1") (pintype "passive"))
      (node (ref "R308") (pin "1") (pinfunction "1_1") (pintype "passive"))
      (node (ref "R313") (pin "1") (pinfunction "1_1") (pintype "passive"))
      (node (ref "TP9") (pin "1") (pinfunction "1_1") (pintype "passive"))
      (node (ref "U29") (pin "10") (pinfunction "VIN_10") (pintype "power_in"))
      (node (ref "U29") (pin "11") (pinfunction "VIN_11") (pintype "power_in"))
      (node (ref "U29") (pin "3") (pinfunction "~{PFM}_3") (pintype "passive"))
      (node (ref "U29") (pin "7") (pinfunction "AIN_7") (pintype "passive"))
      (node (ref "U29") (pin "8") (pinfunction "VIN_8") (pintype "power_in"))
      (node (ref "U29") (pin "9") (pinfunction "VIN_9") (pintype "power_in"))
      (node (ref "U29") (pin "IN") (pinfunction "IN_IN") (pintype "passive"))
      (node (ref "U41") (pin "2") (pinfunction "VCC_2") (pintype "power_in"))
      (node (ref "U5") (pin "10") (pinfunction "VIN_10") (pintype "power_in"))
      (node (ref "U5") (pin "11") (pinfunction "VIN_11") (pintype "power_in"))
      (node (ref "U5") (pin "3") (pinfunction "~{PFM}_3") (pintype "passive"))
      (node (ref "U5") (pin "7") (pinfunction "AIN_7") (pintype "passive"))
      (node (ref "U5") (pin "8") (pinfunction "VIN_8") (pintype "power_in"))
      (node (ref "U5") (pin "9") (pinfunction "VIN_9") (pintype "power_in"))
      (node (ref "U5") (pin "IN") (pinfunction "IN_IN") (pintype "passive"))
    )
    (net (code "11") (name "GND") (class "Default")
      (node (ref "C100") (pin "2") (pinfunction "2_2") (pintype "passive"))
      (node (ref "C101") (pin "2") (pinfunction "2_2") (pintype "passive"))
      (node (ref "C102") (pin "2") (pinfunction "2_2") (pintype "passive"))
      (node (ref "C103") (pin "2") (pinfunction "2_2") (pintype "passive"))
      (node (ref "C104") (pin "2") (pinfunction "2_2") (pintype "passive"))
      (node (ref "C105") (pin "2") (pinfunction "2_2") (pintype "passive"))
      (node (ref "C106") (pin "2") (pinfunction "2_2") (pintype "passive"))
      (node (ref "C107") (pin "2") (pinfunction "2_2") (pintype "passive"))
      (node (ref "C108") (pin "2") (pinfunction "2_2") (pintype "passive"))
      (node (ref "C109") (pin "2") (pinfunction "2_2") (pintype "passive"))
      (node (ref "C416") (pin "2") (pinfunction "2_2") (pintype "passive"))
      (node (ref "C417") (pin "2") (pinfunction "2_2") (pintype "passive"))
      (node (ref "C82") (pin "2") (pinfunction "2_2") (pintype "passive"))
      (node (ref "C83") (pin "2") (pinfunction "2_2") (pintype "passive"))
      (node (ref "C84") (pin "2") (pinfunction "2_2") (pintype "passive"))
      (node (ref "C85") (pin "2") (pinfunction "2_2") (pintype "passive"))
      (node (ref "C86") (pin "2") (pinfunction "2_2") (pintype "passive"))
      (node (ref "C87") (pin "2") (pinfunction "2_2") (pintype "passive"))
      (node (ref "C88") (pin "2") (pinfunction "2_2") (pintype "passive"))
      (node (ref "C89") (pin "2") (pinfunction "2_2") (pintype "passive"))
      (node (ref "C90") (pin "2") (pinfunction "2_2") (pintype "passive"))
      (node (ref "C91") (pin "2") (pinfunction "2_2") (pintype "passive"))
      (node (ref "C92") (pin "2") (pinfunction "2_2") (pintype "passive"))
      (node (ref "C93") (pin "2") (pinfunction "2_2") (pintype "passive"))
      (node (ref "C94") (pin "2") (pinfunction "2_2") (pintype "passive"))
      (node (ref "C95") (pin "2") (pinfunction "2_2") (pintype "passive"))
      (node (ref "C97") (pin "2") (pinfunction "2_2") (pintype "passive"))
      (node (ref "C98") (pin "2") (pinfunction "2_2") (pintype "passive"))
      (node (ref "C99") (pin "2") (pinfunction "2_2") (pintype "passive"))
      (node (ref "D17") (pin "K") (pinfunction "K_K") (pintype "passive"))
      (node (ref "D20") (pin "K") (pinfunction "K_K") (pintype "passive"))
      (node (ref "D21") (pin "K") (pinfunction "K_K") (pintype "passive"))
      (node (ref "D23") (pin "A") (pinfunction "A_A") (pintype "passive"))
      (node (ref "D24") (pin "A") (pinfunction "A_A") (pintype "passive"))
      (node (ref "L2") (pin "3") (pinfunction "3_3") (pintype "passive"))
      (node (ref "R19") (pin "2") (pinfunction "2_2") (pintype "passive"))
      (node (ref "R20") (pin "2") (pinfunction "2_2") (pintype "passive"))
      (node (ref "R21") (pin "2") (pinfunction "2_2") (pintype "passive"))
      (node (ref "R25") (pin "2") (pinfunction "2_2") (pintype "passive"))
      (node (ref "R28") (pin "2") (pinfunction "2_2") (pintype "passive"))
      (node (ref "R29") (pin "2") (pinfunction "2_2") (pintype "passive"))
      (node (ref "R30") (pin "2") (pinfunction "2_2") (pintype "passive"))
      (node (ref "R31") (pin "2") (pinfunction "2_2") (pintype "passive"))
      (node (ref "R315") (pin "2") (pinfunction "2_2") (pintype "passive"))
      (node (ref "R316") (pin "2") (pinfunction "2_2") (pintype "passive"))
      (node (ref "R317") (pin "2") (pinfunction "2_2") (pintype "passive"))
      (node (ref "R318") (pin "2") (pinfunction "2_2") (pintype "passive"))
      (node (ref "U13") (pin "5") (pinfunction "GND_5") (pintype "power_in"))
      (node (ref "U29") (pin "12") (pinfunction "PGND_12") (pintype "power_in"))
      (node (ref "U29") (pin "13") (pinfunction "PGND_13") (pintype "power_in"))
      (node (ref "U29") (pin "14") (pinfunction "PGND_14") (pintype "power_in"))
      (node (ref "U29") (pin "15") (pinfunction "PGND_15") (pintype "power_in"))
      (node (ref "U29") (pin "16") (pinfunction "PGND_16") (pintype "power_in"))
      (node (ref "U29") (pin "17") (pinfunction "PGND_17") (pintype "power_in"))
      (node (ref "U29") (pin "18") (pinfunction "PGND_18") (pintype "power_in"))
      (node (ref "U29") (pin "19") (pinfunction "PGND_19") (pintype "power_in"))
      (node (ref "U29") (pin "26") (pinfunction "PGND_26") (pintype "power_in"))
      (node (ref "U29") (pin "29") (pinfunction "AGND_29") (pintype "power_in"))
      (node (ref "U29") (pin "4") (pinfunction "AGND_4") (pintype "power_in"))
      (node (ref "U29") (pin "AGND") (pinfunction "AGND_AGND") (pintype "power_in"))
      (node (ref "U41") (pin "FIN") (pinfunction "GND_FIN") (pintype "power_in"))
      (node (ref "U5") (pin "12") (pinfunction "PGND_12") (pintype "power_in"))
      (node (ref "U5") (pin "13") (pinfunction "PGND_13") (pintype "power_in"))
      (node (ref "U5") (pin "14") (pinfunction "PGND_14") (pintype "power_in"))
      (node (ref "U5") (pin "15") (pinfunction "PGND_15") (pintype "power_in"))
      (node (ref "U5") (pin "16") (pinfunction "PGND_16") (pintype "power_in"))
      (node (ref "U5") (pin "17") (pinfunction "PGND_17") (pintype "power_in"))
      (node (ref "U5") (pin "18") (pinfunction "PGND_18") (pintype "power_in"))
      (node (ref "U5") (pin "19") (pinfunction "PGND_19") (pintype "power_in"))
      (node (ref "U5") (pin "26") (pinfunction "PGND_26") (pintype "power_in"))
      (node (ref "U5") (pin "29") (pinfunction "AGND_29") (pintype "power_in"))
      (node (ref "U5") (pin "4") (pinfunction "AGND_4") (pintype "power_in"))
      (node (ref "U5") (pin "AGND") (pinfunction "AGND_AGND") (pintype "power_in"))
      (node (ref "U7") (pin "FIN") (pinfunction "GND_FIN") (pintype "power_in"))
      (node (ref "U8") (pin "FIN") (pinfunction "GND_FIN") (pintype "power_in"))
    )
    (net (code "12") (name "Net-(C81-Pad1)") (class "Default")
      (node (ref "C81") (pin "1") (pinfunction "1_1") (pintype "passive"))
      (node (ref "L1") (pin "1") (pinfunction "1_1") (pintype "passive"))
      (node (ref "U29") (pin "20") (pinfunction "LX_20") (pintype "passive"))
      (node (ref "U29") (pin "21") (pinfunction "LX_21") (pintype "passive"))
      (node (ref "U29") (pin "22") (pinfunction "LX_22") (pintype "passive"))
      (node (ref "U29") (pin "23") (pinfunction "LX_23") (pintype "passive"))
      (node (ref "U29") (pin "24") (pinfunction "LX_24") (pintype "passive"))
      (node (ref "U29") (pin "25") (pinfunction "LX_25") (pintype "passive"))
      (node (ref "U29") (pin "LX") (pinfunction "LX_LX") (pintype "passive"))
    )
    (net (code "13") (name "Net-(C96-Pad1)") (class "Default")
      (node (ref "C96") (pin "1") (pinfunction "1_1") (pintype "passive"))
      (node (ref "L8") (pin "1") (pinfunction "1_1") (pintype "passive"))
      (node (ref "U5") (pin "20") (pinfunction "LX_20") (pintype "passive"))
      (node (ref "U5") (pin "21") (pinfunction "LX_21") (pintype "passive"))
      (node (ref "U5") (pin "22") (pinfunction "LX_22") (pintype "passive"))
      (node (ref "U5") (pin "23") (pinfunction "LX_23") (pintype "passive"))
      (node (ref "U5") (pin "24") (pinfunction "LX_24") (pintype "passive"))
      (node (ref "U5") (pin "25") (pinfunction "LX_25") (pintype "passive"))
      (node (ref "U5") (pin "LX") (pinfunction "LX_LX") (pintype "passive"))
    )
    (net (code "14") (name "Net-(D2-Pad1)") (class "Default")
      (node (ref "D2") (pin "1") (pinfunction "1_1") (pintype "passive"))
      (node (ref "D2") (pin "2") (pinfunction "2_2") (pintype "passive"))
      (node (ref "D3") (pin "1") (pinfunction "1_1") (pintype "passive"))
      (node (ref "F1") (pin "2") (pinfunction "2_2") (pintype "passive"))
      (node (ref "R310") (pin "1") (pinfunction "1_1") (pintype "passive"))
    )
    (net (code "15") (name "Net-(D2-PadK)") (class "Default")
      (node (ref "D2") (pin "K") (pinfunction "K_K") (pintype "passive"))
      (node (ref "L2") (pin "1") (pinfunction "1_1") (pintype "passive"))
    )
    (net (code "16") (name "Net-(D17-PadA)") (class "Default")
      (node (ref "D17") (pin "A") (pinfunction "A_A") (pintype "passive"))
      (node (ref "R308") (pin "2") (pinfunction "2_2") (pintype "passive"))
    )
    (net (code "17") (name "Net-(D18-PadA)") (class "Default")
      (node (ref "D18") (pin "A") (pinfunction "A_A") (pintype "passive"))
      (node (ref "R309") (pin "2") (pinfunction "2_2") (pintype "passive"))
    )
    (net (code "18") (name "Net-(D19-PadA)") (class "Default")
      (node (ref "D19") (pin "A") (pinfunction "A_A") (pintype "passive"))
      (node (ref "R310") (pin "2") (pinfunction "2_2") (pintype "passive"))
    )
    (net (code "19") (name "Net-(D20-PadA)") (class "Default")
      (node (ref "D20") (pin "A") (pinfunction "A_A") (pintype "passive"))
      (node (ref "R311") (pin "2") (pinfunction "2_2") (pintype "passive"))
    )
    (net (code "20") (name "Net-(D21-PadA)") (class "Default")
      (node (ref "D21") (pin "A") (pinfunction "A_A") (pintype "passive"))
      (node (ref "R312") (pin "2") (pinfunction "2_2") (pintype "passive"))
    )
    (net (code "21") (name "Net-(F1-Pad1)") (class "Default")
      (node (ref "F1") (pin "1") (pinfunction "1_1") (pintype "passive"))
      (node (ref "SW6") (pin "2") (pinfunction "2_2") (pintype "passive"))
    )
    (net (code "22") (name "Net-(Q13-G)") (class "Default")
      (node (ref "Q13") (pin "3") (pinfunction "G_3") (pintype "passive"))
      (node (ref "U13") (pin "10") (pinfunction "GATE_10") (pintype "passive"))
    )
    (net (code "23") (name "Net-(U5-BST)") (class "Default")
      (node (ref "C96") (pin "2") (pinfunction "2_2") (pintype "passive"))
      (node (ref "U5") (pin "27") (pinfunction "BST_27") (pintype "passive"))
    )
    (net (code "24") (name "Net-(U5-EN)") (class "Default")
      (node (ref "D24") (pin "K") (pinfunction "K_K") (pintype "passive"))
      (node (ref "R24") (pin "2") (pinfunction "2_2") (pintype "passive"))
      (node (ref "R318") (pin "1") (pinfunction "1_1") (pintype "passive"))
      (node (ref "U5") (pin "2") (pinfunction "EN_2") (pintype "input"))
    )
    (net (code "25") (name "Net-(U5-FB_(0.8V))") (class "Default")
      (node (ref "R23") (pin "2") (pinfunction "2_2") (pintype "passive"))
      (node (ref "R25") (pin "1") (pinfunction "1_1") (pintype "passive"))
      (node (ref "U5") (pin "5") (pinfunction "FB_(0.8V)_5") (pintype "passive"))
    )
    (net (code "26") (name "Net-(U5-PGOOD)") (class "Default")
      (node (ref "R319") (pin "2") (pinfunction "2_2") (pintype "passive"))
      (node (ref "U5") (pin "1") (pinfunction "PGOOD_1") (pintype "output"))
    )
    (net (code "27") (name "Net-(U5-SS)") (class "Default")
      (node (ref "C105") (pin "1") (pinfunction "1_1") (pintype "passive"))
      (node (ref "U5") (pin "30") (pinfunction "SS_30") (pintype "passive"))
    )
    (net (code "28") (name "Net-(U5-TON)") (class "Default")
      (node (ref "R22") (pin "2") (pinfunction "2_2") (pintype "passive"))
      (node (ref "U5") (pin "6") (pinfunction "TON_6") (pintype "passive"))
    )
    (net (code "29") (name "Net-(U5-VCC)") (class "Default")
      (node (ref "C104") (pin "1") (pinfunction "1_1") (pintype "passive"))
      (node (ref "U5") (pin "28") (pinfunction "VCC_28") (pintype "passive"))
    )
    (net (code "30") (name "Net-(U7-CTL)") (class "Default")
      (node (ref "R28") (pin "1") (pinfunction "1_1") (pintype "passive"))
      (node (ref "R305") (pin "2") (pinfunction "2_2") (pintype "passive"))
      (node (ref "R307") (pin "2") (pinfunction "2_2") (pintype "passive"))
      (node (ref "U7") (pin "1") (pinfunction "CTL_1") (pintype "passive"))
    )
    (net (code "31") (name "Net-(U7-C_(ADJ))") (class "Default")
      (node (ref "R26") (pin "2") (pinfunction "2_2") (pintype "passive"))
      (node (ref "R30") (pin "1") (pinfunction "1_1") (pintype "passive"))
      (node (ref "U7") (pin "5") (pinfunction "C_(ADJ)_5") (pintype "power_in"))
    )
    (net (code "32") (name "Net-(U8-C_(ADJ))") (class "Default")
      (node (ref "R27") (pin "2") (pinfunction "2_2") (pintype "passive"))
      (node (ref "R31") (pin "1") (pinfunction "1_1") (pintype "passive"))
      (node (ref "U8") (pin "5") (pinfunction "C_(ADJ)_5") (pintype "power_in"))
    )
    (net (code "33") (name "Net-(U13-OUT)") (class "Default")
      (node (ref "R17") (pin "1") (pinfunction "1_1") (pintype "passive"))
      (node (ref "U13") (pin "9") (pinfunction "OUT_9") (pintype "passive"))
    )
    (net (code "34") (name "Net-(U13-OVLO_(2.5V))") (class "Default")
      (node (ref "R18") (pin "2") (pinfunction "2_2") (pintype "passive"))
      (node (ref "R21") (pin "1") (pinfunction "1_1") (pintype "passive"))
      (node (ref "U13") (pin "4") (pinfunction "OVLO_(2.5V)_4") (pintype "passive"))
    )
    (net (code "35") (name "Net-(U13-PGD)") (class "Default")
      (node (ref "R17") (pin "2") (pinfunction "2_2") (pintype "passive"))
      (node (ref "U13") (pin "8") (pinfunction "PGD_8") (pintype "open_collector"))
    )
    (net (code "36") (name "Net-(U13-PWR)") (class "Default")
      (node (ref "R20") (pin "1") (pinfunction "1_1") (pintype "passive"))
      (node (ref "U13") (pin "7") (pinfunction "PWR_7") (pintype "passive"))
    )
    (net (code "37") (name "Net-(U13-SEN)") (class "Default")
      (node (ref "Q13") (pin "1") (pinfunction "D_1") (pintype "passive"))
      (node (ref "Q13") (pin "2") (pinfunction "D_2") (pintype "passive"))
      (node (ref "Q13") (pin "5") (pinfunction "D_5") (pintype "passive"))
      (node (ref "Q13") (pin "6") (pinfunction "D_6") (pintype "passive"))
      (node (ref "Q13") (pin "D") (pinfunction "D_D") (pintype "passive"))
      (node (ref "R13") (pin "2") (pinfunction "2_2") (pintype "passive"))
      (node (ref "U13") (pin "1") (pinfunction "SEN_1") (pintype "passive"))
    )
    (net (code "38") (name "Net-(U13-TIMER)") (class "Default")
      (node (ref "C95") (pin "1") (pinfunction "1_1") (pintype "passive"))
      (node (ref "U13") (pin "6") (pinfunction "TIMER_6") (pintype "passive"))
    )
    (net (code "39") (name "Net-(U13-UVLO_(2.5V))") (class "Default")
      (node (ref "R14") (pin "2") (pinfunction "2_2") (pintype "passive"))
      (node (ref "R18") (pin "1") (pinfunction "1_1") (pintype "passive"))
      (node (ref "U13") (pin "3") (pinfunction "UVLO_(2.5V)_3") (pintype "passive"))
    )
    (net (code "40") (name "Net-(U29-BST)") (class "Default")
      (node (ref "C81") (pin "2") (pinfunction "2_2") (pintype "passive"))
      (node (ref "U29") (pin "27") (pinfunction "BST_27") (pintype "passive"))
    )
    (net (code "41") (name "Net-(U29-EN)") (class "Default")
      (node (ref "D23") (pin "K") (pinfunction "K_K") (pintype "passive"))
      (node (ref "R16") (pin "2") (pinfunction "2_2") (pintype "passive"))
      (node (ref "R317") (pin "1") (pinfunction "1_1") (pintype "passive"))
      (node (ref "U29") (pin "2") (pinfunction "EN_2") (pintype "input"))
    )
    (net (code "42") (name "Net-(U29-FB_(0.8V))") (class "Default")
      (node (ref "R15") (pin "2") (pinfunction "2_2") (pintype "passive"))
      (node (ref "R19") (pin "1") (pinfunction "1_1") (pintype "passive"))
      (node (ref "U29") (pin "5") (pinfunction "FB_(0.8V)_5") (pintype "passive"))
    )
    (net (code "43") (name "Net-(U29-SS)") (class "Default")
      (node (ref "C94") (pin "1") (pinfunction "1_1") (pintype "passive"))
      (node (ref "U29") (pin "30") (pinfunction "SS_30") (pintype "passive"))
    )
    (net (code "44") (name "Net-(U29-TON)") (class "Default")
      (node (ref "R12") (pin "2") (pinfunction "2_2") (pintype "passive"))
      (node (ref "U29") (pin "6") (pinfunction "TON_6") (pintype "passive"))
    )
    (net (code "45") (name "Net-(U29-VCC)") (class "Default")
      (node (ref "C93") (pin "1") (pinfunction "1_1") (pintype "passive"))
      (node (ref "U29") (pin "28") (pinfunction "VCC_28") (pintype "passive"))
    )
    (net (code "46") (name "Net-(U41-CTL)") (class "Default")
      (node (ref "R313") (pin "2") (pinfunction "2_2") (pintype "passive"))
      (node (ref "R315") (pin "1") (pinfunction "1_1") (pintype "passive"))
      (node (ref "R320") (pin "2") (pinfunction "2_2") (pintype "passive"))
      (node (ref "U41") (pin "1") (pinfunction "CTL_1") (pintype "passive"))
    )
    (net (code "47") (name "Net-(U41-C_(ADJ))") (class "Default")
      (node (ref "R314") (pin "2") (pinfunction "2_2") (pintype "passive"))
      (node (ref "R316") (pin "1") (pinfunction "1_1") (pintype "passive"))
      (node (ref "U41") (pin "5") (pinfunction "C_(ADJ)_5") (pintype "power_in"))
    )
    (net (code "48") (name "VIN") (class "Default")
      (node (ref "C82") (pin "1") (pinfunction "1_1") (pintype "passive"))
      (node (ref "C86") (pin "1") (pinfunction "1_1") (pintype "passive"))
      (node (ref "L2") (pin "4") (pinfunction "4_4") (pintype "passive"))
      (node (ref "R13") (pin "1") (pinfunction "1_1") (pintype "passive"))
      (node (ref "R14") (pin "1") (pinfunction "1_1") (pintype "passive"))
      (node (ref "TP8") (pin "1") (pinfunction "1_1") (pintype "passive"))
      (node (ref "U13") (pin "2") (pinfunction "VIN_2") (pintype "power_in"))
    )
    (net (code "49") (name "unconnected-(J13-2-Pad3)") (class "Default")
      (node (ref "J13") (pin "3") (pinfunction "2_3") (pintype "passive+no_connect"))
    )
    (net (code "50") (name "unconnected-(SW6-Pad3)") (class "Default")
      (node (ref "SW6") (pin "3") (pinfunction "3_3") (pintype "passive+no_connect"))
    )
    (net (code "51") (name "unconnected-(U29-PGOOD-Pad1)") (class "Default")
      (node (ref "U29") (pin "1") (pinfunction "PGOOD_1") (pintype "output+no_connect"))
    )
  )
)
